# Charger_S_CAP_BAT.net
KiCad netlist of a schematic drawn in Altium Designer
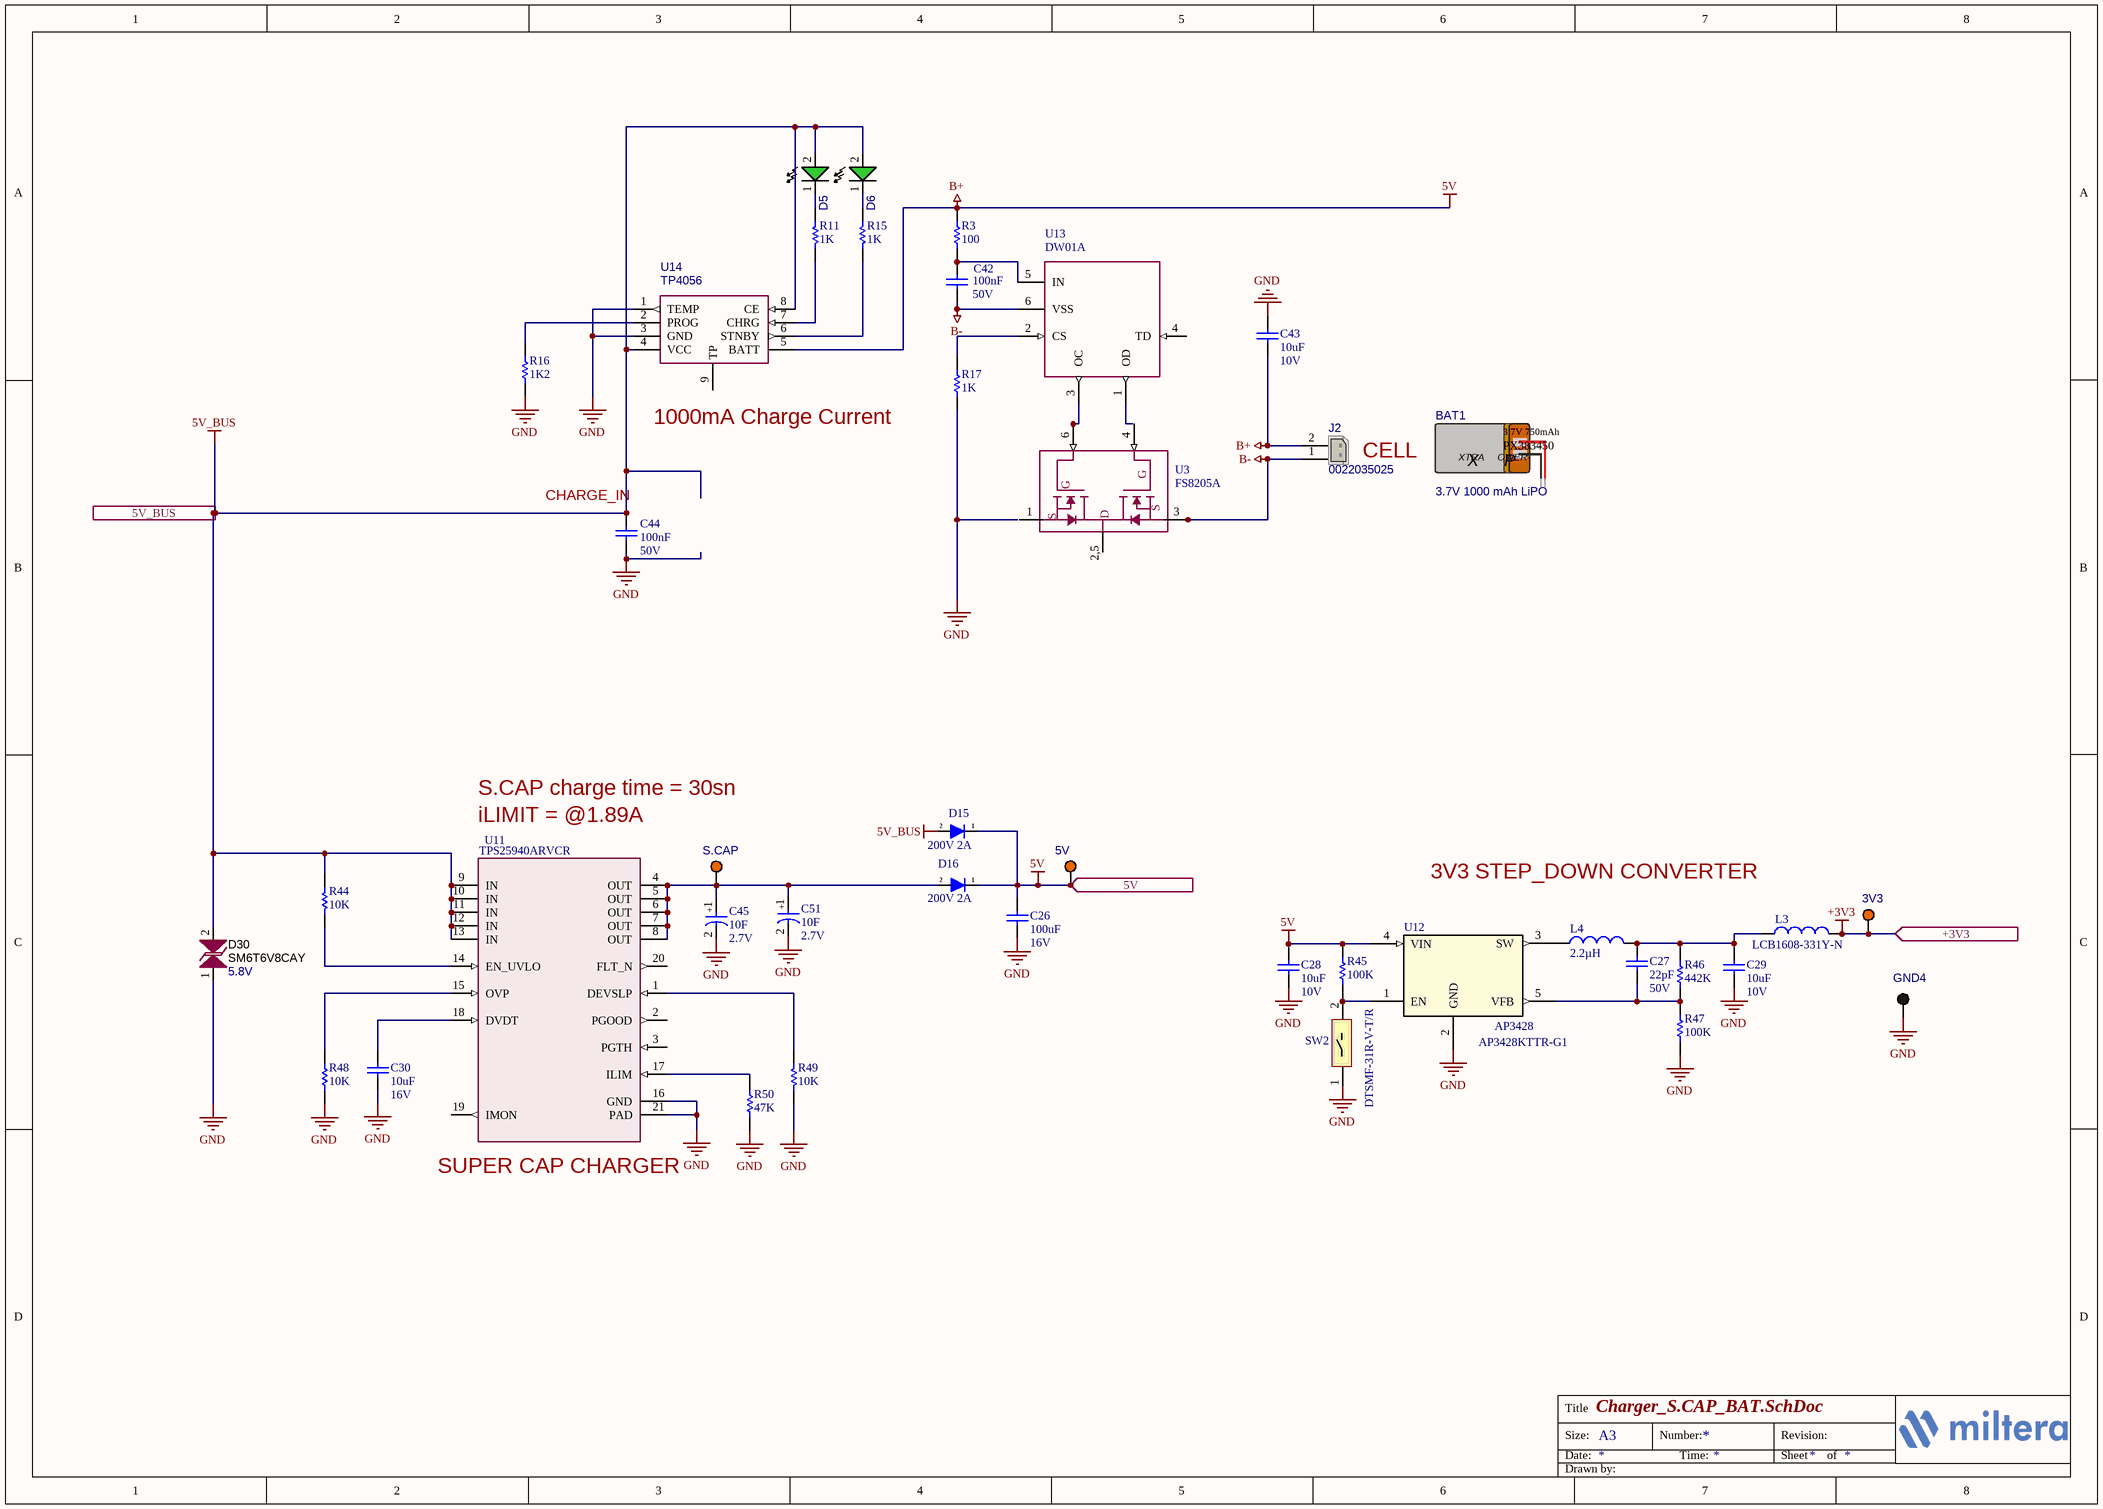
[diagram p0: Charger_S.CAP_BAT.SchDoc]

(export (version "E")
  (design (tool "Eeschema 10.0.6"))
  (components
    (comp (ref "3V3")
      (value "L-KLS8-TP5003")
      (footprint "TEST_POINT_ORANGE")
      (description "PC TEST POINT MINIATURE ORANGE 2.54MMX4.60MM")
      (fields (field (name "MANUFACTURER") "KLS ELECTRONIC"))
      (libsource (lib "Hardware_Fasteners") (part "5003"))
    )
    (comp (ref "5V")
      (value "L-KLS8-TP5003")
      (footprint "TEST_POINT_ORANGE")
      (description "PC TEST POINT MINIATURE ORANGE 2.54MMX4.60MM")
      (fields (field (name "MANUFACTURER") "KLS ELECTRONIC"))
      (libsource (lib "Hardware_Fasteners") (part "5003"))
    )
    (comp (ref "BAT1")
      (value "3.7V 1000 mAh LiPO")
      (description "Power-Xtra PX603450 3.7V 1000 mAh Li-Polymer Pil (Devreli/1.5A)")
      (fields (field (name "MANUFACTURER") "Power-Xtra") (field (name "MANUFACTURER PART NUMBER") "PX603450"))
      (libsource (lib "Power_Circuit_Protection") (part "PX383450"))
    )
    (comp (ref "C26")
      (value "100uF")
      (footprint "CAP_1210")
      (description "MLCC (3225) 1210 100uF 16VDC ±20% X5R")
      (fields
        (field (name "VOLTAGE") "16V")
        (field (name "MANUFACTURER") "KEMET")
        (field (name "MANUFACTURER PART NUMBER") "C1210C107M4PACTU")
      )
      (libsource (lib "open-components") (part "CAP"))
    )
    (comp (ref "C27")
      (value "22pF")
      (footprint "CAP_0603")
      (description "MLCC 0603 22pF 50VDC ±5% C0G (NP0)")
      (fields
        (field (name "VOLTAGE") "50V")
        (field (name "MANUFACTURER") "Samsung")
        (field (name "MANUFACTURER PART NUMBER") "CL10C220JB8NNNC")
      )
      (libsource (lib "open-components") (part "CAP"))
    )
    (comp (ref "C28")
      (value "10uF")
      (footprint "CAP_0603")
      (description "MLCC (1608) 0603 10uF 10VDC ±20% X5R")
      (fields
        (field (name "VOLTAGE") "10V")
        (field (name "MANUFACTURER") "Samsung")
        (field (name "MANUFACTURER PART NUMBER") "CL10A106MP8NNNC")
      )
      (libsource (lib "open-components") (part "CAP"))
    )
    (comp (ref "C29")
      (value "10uF")
      (footprint "CAP_0603")
      (description "MLCC (1608) 0603 10uF 10VDC ±20% X5R")
      (fields
        (field (name "VOLTAGE") "10V")
        (field (name "MANUFACTURER") "Samsung")
        (field (name "MANUFACTURER PART NUMBER") "CL10A106MP8NNNC")
      )
      (libsource (lib "open-components") (part "CAP"))
    )
    (comp (ref "C30")
      (value "10uF")
      (footprint "CAP_0603")
      (description "MLCC (1608) 0603 10uF 16VDC ±20% X5R")
      (fields
        (field (name "VOLTAGE") "16V")
        (field (name "MANUFACTURER") "Samsung")
        (field (name "MANUFACTURER PART NUMBER") "CL10A106MO8NQNC")
      )
      (libsource (lib "open-components") (part "CAP"))
    )
    (comp (ref "C42")
      (value "100nF")
      (footprint "CAP_0603")
      (description "CAP CER 100nF 50VDC %10 X7R SMD")
      (fields
        (field (name "VOLTAGE") "50V")
        (field (name "MANUFACTURER") "Samsung")
        (field (name "MANUFACTURER PART NUMBER") "CL10B104KB8NNNL")
      )
      (libsource (lib "open-components") (part "CAP"))
    )
    (comp (ref "C43")
      (value "10uF")
      (footprint "CAP_0603")
      (description "MLCC (1608) 0603 10uF 10VDC ±20% X5R")
      (fields
        (field (name "VOLTAGE") "10V")
        (field (name "MANUFACTURER") "Samsung")
        (field (name "MANUFACTURER PART NUMBER") "CL10A106MP8NNNC")
      )
      (libsource (lib "open-components") (part "CAP"))
    )
    (comp (ref "C44")
      (value "100nF")
      (footprint "CAP_0603")
      (description "CAP CER 100nF 50VDC %10 X7R SMD")
      (fields
        (field (name "VOLTAGE") "50V")
        (field (name "MANUFACTURER") "Samsung")
        (field (name "MANUFACTURER PART NUMBER") "CL10B104KB8NNNL")
      )
      (libsource (lib "open-components") (part "CAP"))
    )
    (comp (ref "C45")
      (value "10F")
      (footprint "BUP002R7L106FK -EX")
      (description "CAP.SUPER 10F 2.7V Radial TYPE 10x25mm")
      (fields
        (field (name "VOLTAGE") "2.7V")
        (field (name "MANUFACTURER") "BIGCAP")
        (field (name "MANUFACTURER PART NUMBER") "BUP002R7L106FK -EX")
      )
      (libsource (lib "open-components") (part "CAP-P"))
    )
    (comp (ref "C51")
      (value "10F")
      (footprint "BUP002R7L106FK -EX")
      (description "CAP.SUPER 10F 2.7V Radial TYPE 10x25mm")
      (fields
        (field (name "VOLTAGE") "2.7V")
        (field (name "MANUFACTURER") "BIGCAP")
        (field (name "MANUFACTURER PART NUMBER") "BUP002R7L106FK -EX")
      )
      (libsource (lib "open-components") (part "CAP-P"))
    )
    (comp (ref "D5")
      (value "PSC-1608U52GC-G4")
      (footprint "LED_0603_GRN")
      (description "LED GREEN WATER CLEAR 0603 SMD")
      (fields (field (name "MANUFACTURER") "HONGLITRONIC"))
      (libsource (lib "Semiconductors") (part "LTST-C190TGKT"))
    )
    (comp (ref "D6")
      (value "PSC-1608U52GC-G4")
      (footprint "LED_0603_GRN")
      (description "LED GREEN WATER CLEAR 0603 SMD")
      (fields (field (name "MANUFACTURER") "HONGLITRONIC"))
      (libsource (lib "Semiconductors") (part "LTST-C190TGKT"))
    )
    (comp (ref "D15")
      (value "ES2D_R1_00001")
      (footprint "SMA")
      (description "DIODE S.FAST SINGLE 2A 200V DO214AC (SMA) SMT")
      (fields (field (name "MANUFACTURER") "PANJIT") (field (name "VOLTAGE") "200V 2A"))
      (libsource (lib "open-components") (part "Diode-SMA"))
    )
    (comp (ref "D16")
      (value "ES2D_R1_00001")
      (footprint "SMA")
      (description "DIODE S.FAST SINGLE 2A 200V DO214AC (SMA) SMT")
      (fields (field (name "MANUFACTURER") "PANJIT") (field (name "VOLTAGE") "200V 2A"))
      (libsource (lib "open-components") (part "Diode-SMA"))
    )
    (comp (ref "D30")
      (value "SM6T6V8CAY")
      (footprint "SMB-Bi")
      (description "DIODE TVS 5.8VWM 13.4VC SMB")
      (fields (field (name "MANUFACTURER") "STMicroelectronics") (field (name "ALTIUM_VALUE") "5.8V"))
      (libsource (lib "Semiconductors") (part "SM6T6V8CAY"))
    )
    (comp (ref "GND4")
      (value "L-KLS8-TP5001")
      (footprint "TEST_POINT_BLACK")
      (description "PC TEST POINT MINIATURE BLACK 2.54MMX4.60MM")
      (fields (field (name "MANUFACTURER") "KLS ELECTRONIC"))
      (libsource (lib "Hardware_Fasteners") (part "5001"))
    )
    (comp (ref "J2")
      (value "0022035025")
      (footprint "0022035025")
      (description "CONN HEADER VERT 2POS 2.5MM")
      (fields (field (name "MANUFACTURER") "Molex"))
      (libsource (lib "Connectors") (part "0022035025"))
    )
    (comp (ref "L3")
      (value "IND")
      (footprint "RES_0603")
      (description "FERRITE BEAD 0603 330R/100MHZ SMD")
      (fields
        (field (name "MANUFACTURER") "Core Master")
        (field (name "MANUFACTURER PART NUMBER") "LCB1608-331Y-N")
      )
      (libsource (lib "open-components") (part "IND"))
    )
    (comp (ref "L4")
      (value "2.2µH")
      (footprint "INDP4040X200M")
      (description "INDUCTOR POWER 2.2UH 3.3X3MM SMD")
      (fields
        (field (name "MANUFACTURER") "Core Master")
        (field (name "MANUFACTURER PART NUMBER") "FPI0302-2R2M")
      )
      (libsource (lib "open-components") (part "IND"))
    )
    (comp (ref "R3")
      (value "100")
      (footprint "RES_1206")
      (description "RES SMD 100 OHM 1% 1/4W 1206")
      (fields
        (field (name "MANUFACTURER") "Yageo")
        (field (name "MANUFACTURER PART NUMBER") "RC1206FR-07100RL")
      )
      (libsource (lib "open-components") (part "RES"))
    )
    (comp (ref "R11")
      (value "1K")
      (footprint "RES_0603")
      (description "RES 0603 1K Ohms 1% 1/10W-S 100PPM")
      (fields
        (field (name "MANUFACTURER") "ROYALOHM")
        (field (name "MANUFACTURER PART NUMBER") "0603SAF1001T5E")
      )
      (libsource (lib "open-components") (part "RES"))
    )
    (comp (ref "R15")
      (value "1K")
      (footprint "RES_0603")
      (description "RES 0603 1K Ohms 1% 1/10W-S 100PPM")
      (fields
        (field (name "MANUFACTURER") "ROYALOHM")
        (field (name "MANUFACTURER PART NUMBER") "0603SAF1001T5E")
      )
      (libsource (lib "open-components") (part "RES"))
    )
    (comp (ref "R16")
      (value "1K2")
      (footprint "RES_0603")
      (description "RES.(1608) 0603 1.2K Ohms 1% 1/10W-S 100PPM")
      (fields
        (field (name "MANUFACTURER") "ROYALOHM")
        (field (name "MANUFACTURER PART NUMBER") "0603SAF1201T5E")
      )
      (libsource (lib "open-components") (part "RES"))
    )
    (comp (ref "R17")
      (value "1K")
      (footprint "RES_0603")
      (description "RES 0603 1K Ohms 1% 1/10W-S 100PPM")
      (fields
        (field (name "MANUFACTURER") "ROYALOHM")
        (field (name "MANUFACTURER PART NUMBER") "0603SAF1001T5E")
      )
      (libsource (lib "open-components") (part "RES"))
    )
    (comp (ref "R44")
      (value "10K")
      (footprint "RES_0603")
      (description "RES 0603 10k Ohms %1 1/10W 100PPM")
      (fields
        (field (name "MANUFACTURER") "ROYALOHM")
        (field (name "MANUFACTURER PART NUMBER") "0603SAF1002T5E")
      )
      (libsource (lib "open-components") (part "RES"))
    )
    (comp (ref "R45")
      (value "100K")
      (footprint "RES_0603")
      (description "RES 0603 100K Ohms 1% 1/10W-S 100PPM")
      (fields
        (field (name "MANUFACTURER") "ROYALOHM")
        (field (name "MANUFACTURER PART NUMBER") "0603SAF1003T5E")
      )
      (libsource (lib "open-components") (part "RES"))
    )
    (comp (ref "R46")
      (value "442K")
      (footprint "RES_0603")
      (description "RES 0603 442K Ohms 1% 1/10W-S 100PPM")
      (fields
        (field (name "MANUFACTURER") "ROYALOHM")
        (field (name "MANUFACTURER PART NUMBER") "0603SAF4423T5E")
      )
      (libsource (lib "open-components") (part "RES"))
    )
    (comp (ref "R47")
      (value "100K")
      (footprint "RES_0603")
      (description "RES 0603 100K Ohms 1% 1/10W-S 100PPM")
      (fields
        (field (name "MANUFACTURER") "ROYALOHM")
        (field (name "MANUFACTURER PART NUMBER") "0603SAF1003T5E")
      )
      (libsource (lib "open-components") (part "RES"))
    )
    (comp (ref "R48")
      (value "10K")
      (footprint "RES_0603")
      (description "RES 0603 10k Ohms %1 1/10W 100PPM")
      (fields
        (field (name "MANUFACTURER") "ROYALOHM")
        (field (name "MANUFACTURER PART NUMBER") "0603SAF1002T5E")
      )
      (libsource (lib "open-components") (part "RES"))
    )
    (comp (ref "R49")
      (value "10K")
      (footprint "RES_0603")
      (description "RES 0603 10k Ohms %1 1/10W 100PPM")
      (fields
        (field (name "MANUFACTURER") "ROYALOHM")
        (field (name "MANUFACTURER PART NUMBER") "0603SAF1002T5E")
      )
      (libsource (lib "open-components") (part "RES"))
    )
    (comp (ref "R50")
      (value "47K")
      (footprint "RES_0603")
      (description "RES 0603 47K Ohms 1% 1/10W-S 100PPM")
      (fields
        (field (name "MANUFACTURER") "ROYALOHM")
        (field (name "MANUFACTURER PART NUMBER") "0603SAF4702T5E")
      )
      (libsource (lib "open-components") (part "RES"))
    )
    (comp (ref "S.CAP")
      (value "L-KLS8-TP5003")
      (footprint "TEST_POINT_ORANGE")
      (description "PC TEST POINT MINIATURE ORANGE 2.54MMX4.60MM")
      (fields (field (name "MANUFACTURER") "KLS ELECTRONIC"))
      (libsource (lib "Hardware_Fasteners") (part "5003"))
    )
    (comp (ref "SW2")
      (value "DTSMF-31R-V-T/R")
      (footprint "tact_switch")
      (description "SWITCH TACT 6.00x3.50 4.30mm 260gF SMT V/T")
      (fields (field (name "MANUFACTURER") "DIPTRONICS"))
      (libsource (lib "DIO_1608SI_R06") (part "Tact_Switch"))
    )
    (comp (ref "U3")
      (value "FS8205A")
      (footprint "SOT23-6")
      (description "MOSFET 20V 9A SOT-23-6")
      (fields (field (name "MANUFACTURER") "TECH PUBLIC"))
      (libsource (lib "Schlib1") (part "FS8205A"))
    )
    (comp (ref "U11")
      (value "TPS25940ARVCR")
      (footprint "20-WFQFN Exposed Pad")
      (description "IC ELECTRONIC FUSE 8% 20WQFN")
      (fields (field (name "MANUFACTURER") "Texas Instruments"))
      (libsource (lib "MTOSOS_R02") (part "TPS25940ARVCR"))
    )
    (comp (ref "U12")
      (value "AP3428")
      (footprint "SOT-23-5")
      (description "Buck Switching Regulator IC Positive Adjustable 0.6V 1 Output 1A SOT-23-5 Thin, TSOT-23-5")
      (fields
        (field (name "MANUFACTURER PART NUMBER") "AP3428KTTR-G1")
        (field (name "MANUFACTURER") "Diodes Incorporated")
      )
      (libsource (lib "open-components") (part "AP3428"))
    )
    (comp (ref "U13")
      (value "DW01A")
      (footprint "SOT23-6")
      (description "IC-01 G BATTERY PROTECTION 1-CELL SOT23-6 FORTU")
      (fields (field (name "MANUFACTURER") "YONGYUTAI"))
      (libsource (lib "Schlib1") (part "DW01A"))
    )
    (comp (ref "U14")
      (value "TP4056")
      (footprint "SOP_8_PowerPAD")
      (description "1A Lithium Battery Charger")
      (fields (field (name "MANUFACTURER") "TPOWER"))
      (libsource (lib "Integrated_Circuit") (part "TP4056-42-SOP8-PP"))
    )
  )
  (nets
    (net (code "1") (name "+3V3") (class "Default")
      (node (ref "3V3") (pin "1") (pintype "passive"))
      (node (ref "L3") (pin "2") (pinfunction "2_2") (pintype "passive"))
    )
    (net (code "2") (name "5V") (class "Default")
      (node (ref "5V") (pin "1") (pintype "passive"))
      (node (ref "C26") (pin "2") (pinfunction "2_2") (pintype "passive"))
      (node (ref "C28") (pin "1") (pinfunction "1_1") (pintype "passive"))
      (node (ref "C43") (pin "2") (pinfunction "2_2") (pintype "passive"))
      (node (ref "D15") (pin "1") (pinfunction "1_1") (pintype "passive"))
      (node (ref "D16") (pin "1") (pinfunction "1_1") (pintype "passive"))
      (node (ref "J2") (pin "2") (pinfunction "2_2") (pintype "passive"))
      (node (ref "R3") (pin "2") (pinfunction "2_2") (pintype "passive"))
      (node (ref "R45") (pin "2") (pinfunction "2_2") (pintype "passive"))
      (node (ref "U12") (pin "4") (pinfunction "VIN_4") (pintype "input"))
      (node (ref "U14") (pin "5") (pinfunction "BATT_5") (pintype "power_in"))
    )
    (net (code "3") (name "5V_BUS") (class "Default")
      (node (ref "C44") (pin "2") (pinfunction "2_2") (pintype "passive"))
      (node (ref "D15") (pin "2") (pinfunction "2_2") (pintype "passive"))
      (node (ref "D30") (pin "2") (pinfunction "2_2") (pintype "passive"))
      (node (ref "D5") (pin "2") (pinfunction "2_2") (pintype "passive"))
      (node (ref "D6") (pin "2") (pinfunction "2_2") (pintype "passive"))
      (node (ref "R44") (pin "2") (pinfunction "2_2") (pintype "passive"))
      (node (ref "U11") (pin "10") (pinfunction "IN_10") (pintype "power_in"))
      (node (ref "U11") (pin "11") (pinfunction "IN_11") (pintype "power_in"))
      (node (ref "U11") (pin "12") (pinfunction "IN_12") (pintype "power_in"))
      (node (ref "U11") (pin "13") (pinfunction "IN_13") (pintype "power_in"))
      (node (ref "U11") (pin "9") (pinfunction "IN_9") (pintype "power_in"))
      (node (ref "U14") (pin "4") (pinfunction "VCC_4") (pintype "power_in"))
      (node (ref "U14") (pin "8") (pinfunction "CE_8") (pintype "input"))
    )
    (net (code "4") (name "B-") (class "Default")
      (node (ref "C42") (pin "1") (pinfunction "1_1") (pintype "passive"))
      (node (ref "J2") (pin "1") (pinfunction "1_1") (pintype "passive"))
      (node (ref "U13") (pin "6") (pinfunction "VSS_6") (pintype "power_in"))
      (node (ref "U3") (pin "3") (pinfunction "S2_3") (pintype "power_in"))
    )
    (net (code "5") (name "GND") (class "Default")
      (node (ref "C26") (pin "1") (pinfunction "1_1") (pintype "passive"))
      (node (ref "C28") (pin "2") (pinfunction "2_2") (pintype "passive"))
      (node (ref "C29") (pin "2") (pinfunction "2_2") (pintype "passive"))
      (node (ref "C30") (pin "1") (pinfunction "1_1") (pintype "passive"))
      (node (ref "C43") (pin "1") (pinfunction "1_1") (pintype "passive"))
      (node (ref "C44") (pin "1") (pinfunction "1_1") (pintype "passive"))
      (node (ref "C45") (pin "2") (pinfunction "2_2") (pintype "passive"))
      (node (ref "C51") (pin "2") (pinfunction "2_2") (pintype "passive"))
      (node (ref "D30") (pin "1") (pinfunction "1_1") (pintype "passive"))
      (node (ref "GND4") (pin "1") (pintype "passive"))
      (node (ref "R16") (pin "1") (pinfunction "1_1") (pintype "passive"))
      (node (ref "R17") (pin "1") (pinfunction "1_1") (pintype "passive"))
      (node (ref "R47") (pin "1") (pinfunction "1_1") (pintype "passive"))
      (node (ref "R48") (pin "2") (pinfunction "2_2") (pintype "passive"))
      (node (ref "R49") (pin "2") (pinfunction "2_2") (pintype "passive"))
      (node (ref "R50") (pin "2") (pinfunction "2_2") (pintype "passive"))
      (node (ref "SW2") (pin "1") (pinfunction "1_1") (pintype "passive"))
      (node (ref "U11") (pin "16") (pinfunction "GND_16") (pintype "power_in"))
      (node (ref "U11") (pin "21") (pinfunction "PAD_21") (pintype "power_in"))
      (node (ref "U12") (pin "2") (pinfunction "GND_2") (pintype "power_in"))
      (node (ref "U14") (pin "1") (pinfunction "TEMP_1") (pintype "output"))
      (node (ref "U14") (pin "3") (pinfunction "GND_3") (pintype "power_in"))
    )
    (net (code "6") (name "Net-(C27-Pad1)") (class "Default")
      (node (ref "C27") (pin "1") (pinfunction "1_1") (pintype "passive"))
      (node (ref "C29") (pin "1") (pinfunction "1_1") (pintype "passive"))
      (node (ref "L3") (pin "1") (pinfunction "1_1") (pintype "passive"))
      (node (ref "L4") (pin "2") (pinfunction "2_2") (pintype "passive"))
      (node (ref "R46") (pin "1") (pinfunction "1_1") (pintype "passive"))
    )
    (net (code "7") (name "Net-(C45-Pad1)") (class "Default")
      (node (ref "C45") (pin "1") (pinfunction "1_1") (pintype "passive"))
      (node (ref "C51") (pin "1") (pinfunction "1_1") (pintype "passive"))
      (node (ref "D16") (pin "2") (pinfunction "2_2") (pintype "passive"))
      (node (ref "S.CAP") (pin "1") (pintype "passive"))
      (node (ref "U11") (pin "4") (pinfunction "OUT_4") (pintype "power_in"))
      (node (ref "U11") (pin "5") (pinfunction "OUT_5") (pintype "power_in"))
      (node (ref "U11") (pin "6") (pinfunction "OUT_6") (pintype "power_in"))
      (node (ref "U11") (pin "7") (pinfunction "OUT_7") (pintype "power_in"))
      (node (ref "U11") (pin "8") (pinfunction "OUT_8") (pintype "power_in"))
    )
    (net (code "8") (name "Net-(D5-Pad1)") (class "Default")
      (node (ref "D5") (pin "1") (pinfunction "1_1") (pintype "passive"))
      (node (ref "R11") (pin "1") (pinfunction "1_1") (pintype "passive"))
    )
    (net (code "9") (name "Net-(D6-Pad1)") (class "Default")
      (node (ref "D6") (pin "1") (pinfunction "1_1") (pintype "passive"))
      (node (ref "R15") (pin "1") (pinfunction "1_1") (pintype "passive"))
    )
    (net (code "10") (name "Net-(U11-DEVSLP)") (class "Default")
      (node (ref "R49") (pin "1") (pinfunction "1_1") (pintype "passive"))
      (node (ref "U11") (pin "1") (pinfunction "DEVSLP_1") (pintype "input"))
    )
    (net (code "11") (name "Net-(U11-DVDT)") (class "Default")
      (node (ref "C30") (pin "2") (pinfunction "2_2") (pintype "passive"))
      (node (ref "U11") (pin "18") (pinfunction "DVDT_18") (pintype "input"))
    )
    (net (code "12") (name "Net-(U11-EN_UVLO)") (class "Default")
      (node (ref "R44") (pin "1") (pinfunction "1_1") (pintype "passive"))
      (node (ref "U11") (pin "14") (pinfunction "EN_UVLO_14") (pintype "input"))
    )
    (net (code "13") (name "Net-(U11-ILIM)") (class "Default")
      (node (ref "R50") (pin "1") (pinfunction "1_1") (pintype "passive"))
      (node (ref "U11") (pin "17") (pinfunction "ILIM_17") (pintype "input"))
    )
    (net (code "14") (name "Net-(U11-OVP)") (class "Default")
      (node (ref "R48") (pin "1") (pinfunction "1_1") (pintype "passive"))
      (node (ref "U11") (pin "15") (pinfunction "OVP_15") (pintype "input"))
    )
    (net (code "15") (name "Net-(U12-EN)") (class "Default")
      (node (ref "R45") (pin "1") (pinfunction "1_1") (pintype "passive"))
      (node (ref "SW2") (pin "2") (pinfunction "2_2") (pintype "passive"))
      (node (ref "U12") (pin "1") (pinfunction "EN_1") (pintype "passive"))
    )
    (net (code "16") (name "Net-(U12-SW)") (class "Default")
      (node (ref "L4") (pin "1") (pinfunction "1_1") (pintype "passive"))
      (node (ref "U12") (pin "3") (pinfunction "SW_3") (pintype "output"))
    )
    (net (code "17") (name "Net-(U12-VFB)") (class "Default")
      (node (ref "C27") (pin "2") (pinfunction "2_2") (pintype "passive"))
      (node (ref "R46") (pin "2") (pinfunction "2_2") (pintype "passive"))
      (node (ref "R47") (pin "2") (pinfunction "2_2") (pintype "passive"))
      (node (ref "U12") (pin "5") (pinfunction "VFB_5") (pintype "output"))
    )
    (net (code "18") (name "Net-(U13-CS)") (class "Default")
      (node (ref "R17") (pin "2") (pinfunction "2_2") (pintype "passive"))
      (node (ref "U13") (pin "2") (pinfunction "CS_2") (pintype "input"))
    )
    (net (code "19") (name "Net-(U13-IN)") (class "Default")
      (node (ref "C42") (pin "2") (pinfunction "2_2") (pintype "passive"))
      (node (ref "R3") (pin "1") (pinfunction "1_1") (pintype "passive"))
      (node (ref "U13") (pin "5") (pinfunction "IN_5") (pintype "power_in"))
    )
    (net (code "20") (name "Net-(U13-OC)") (class "Default")
      (node (ref "U13") (pin "3") (pinfunction "OC_3") (pintype "output"))
      (node (ref "U3") (pin "6") (pinfunction "G1_6") (pintype "input"))
    )
    (net (code "21") (name "Net-(U14-CHRG)") (class "Default")
      (node (ref "R11") (pin "2") (pinfunction "2_2") (pintype "passive"))
      (node (ref "U14") (pin "7") (pinfunction "CHRG_7") (pintype "input"))
    )
    (net (code "22") (name "Net-(U14-PROG)") (class "Default")
      (node (ref "R16") (pin "2") (pinfunction "2_2") (pintype "passive"))
      (node (ref "U14") (pin "2") (pinfunction "PROG_2") (pintype "open_emitter"))
    )
    (net (code "23") (name "Net-(U14-STNBY)") (class "Default")
      (node (ref "R15") (pin "2") (pinfunction "2_2") (pintype "passive"))
      (node (ref "U14") (pin "6") (pinfunction "STNBY_6") (pintype "output"))
    )
    (net (code "24") (name "unconnected-(U3-D1{slash}D2-Pad2)") (class "Default")
      (node (ref "U3") (pin "2") (pinfunction "D1/D2_2") (pintype "passive"))
      (node (ref "U3") (pin "5") (pinfunction "D1/D2_5") (pintype "passive"))
    )
    (net (code "25") (name "unconnected-(U3-G2-Pad4)") (class "Default")
      (node (ref "U3") (pin "4") (pinfunction "G2_4") (pintype "input"))
    )
    (net (code "26") (name "unconnected-(U3-S1-Pad1)") (class "Default")
      (node (ref "U3") (pin "1") (pinfunction "S1_1") (pintype "open_emitter"))
    )
    (net (code "27") (name "unconnected-(U11-FLT_N-Pad20)") (class "Default")
      (node (ref "U11") (pin "20") (pinfunction "FLT_N_20") (pintype "output"))
    )
    (net (code "28") (name "unconnected-(U11-IMON-Pad19)") (class "Default")
      (node (ref "U11") (pin "19") (pinfunction "IMON_19") (pintype "output"))
    )
    (net (code "29") (name "unconnected-(U11-PGOOD-Pad2)") (class "Default")
      (node (ref "U11") (pin "2") (pinfunction "PGOOD_2") (pintype "output"))
    )
    (net (code "30") (name "unconnected-(U11-PGTH-Pad3)") (class "Default")
      (node (ref "U11") (pin "3") (pinfunction "PGTH_3") (pintype "input"))
    )
    (net (code "31") (name "unconnected-(U13-OD-Pad1)") (class "Default")
      (node (ref "U13") (pin "1") (pinfunction "OD_1") (pintype "output"))
    )
    (net (code "32") (name "unconnected-(U13-TD-Pad4)") (class "Default")
      (node (ref "U13") (pin "4") (pinfunction "TD_4") (pintype "input"))
    )
    (net (code "33") (name "unconnected-(U14-TP-Pad9)") (class "Default")
      (node (ref "U14") (pin "9") (pinfunction "TP_9") (pintype "passive"))
    )
  )
)
